# solar_collector_controller_V2.net
KiCad netlist of a schematic drawn in EAGLE
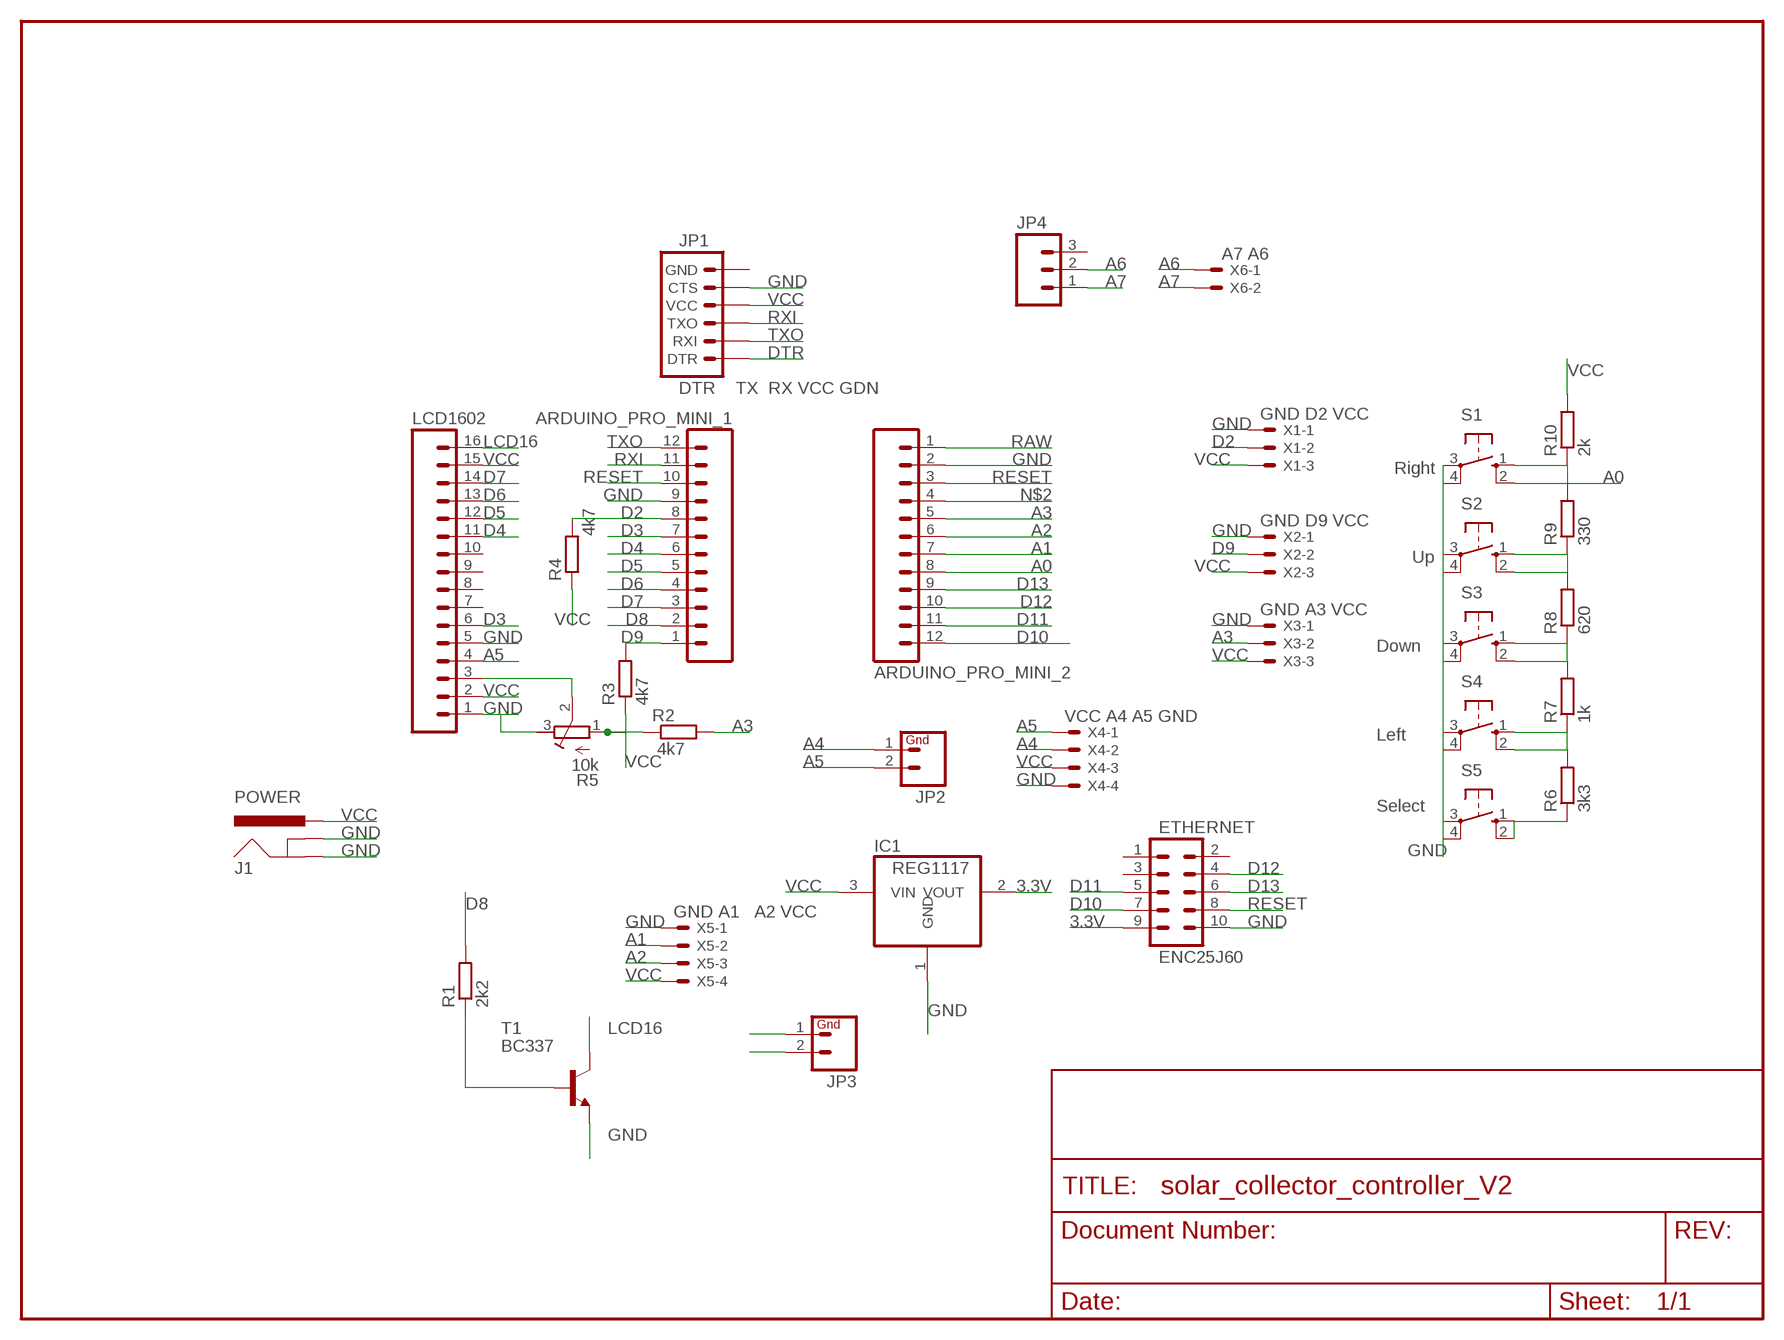
[diagram p0: schematic, sheet 1]

(export (version "E")
  (design (tool "Eeschema 10.0.6"))
  (components
    (comp (ref "ARDUINO_PRO_MINI_1")
      (value "M12PTH")
      (footprint "eagle-import:1X12")
      (libsource (lib "eagle-import") (part "M12PTH"))
    )
    (comp (ref "ARDUINO_PRO_MINI_2")
      (value "M12PTH")
      (footprint "eagle-import:1X12")
      (libsource (lib "eagle-import") (part "M12PTH"))
    )
    (comp (ref "ETHERNET")
      (value "ENC25J60")
      (footprint "eagle-import:AVR_ICSP")
      (libsource (lib "eagle-import") (part "M05X2PTH"))
    )
    (comp (ref "IC1")
      (value "REG1117")
      (footprint "eagle-import:SOT223")
      (libsource (lib "eagle-import") (part "REG1117"))
    )
    (comp (ref "J1")
      (value "POWER")
      (footprint "eagle-import:POWER_JACK_PTH_LOCK")
      (libsource (lib "eagle-import") (part "POWER_JACKPTH_LOCK"))
    )
    (comp (ref "JP1")
      (value "DTR TX RX VCC GDN")
      (footprint "eagle-import:1X06")
      (libsource (lib "eagle-import") (part "ARDUINO_SERIAL_PROGRAMPTH"))
    )
    (comp (ref "JP2")
      (value "M02PTH")
      (footprint "eagle-import:1X02")
      (libsource (lib "eagle-import") (part "M02PTH"))
    )
    (comp (ref "JP3")
      (value "M02PTH")
      (footprint "eagle-import:1X02")
      (libsource (lib "eagle-import") (part "M02PTH"))
    )
    (comp (ref "JP4")
      (value "M03PTH")
      (footprint "eagle-import:1X03")
      (libsource (lib "eagle-import") (part "M03PTH"))
    )
    (comp (ref "LCD1602")
      (value "HEADER-16P-2.54")
      (footprint "eagle-import:16P-2.54")
      (libsource (lib "eagle-import") (part "HEADER-16P-2.54"))
    )
    (comp (ref "R1")
      (value "2k2")
      (footprint "eagle-import:0207_10")
      (libsource (lib "eagle-import") (part "R-EU_0207/10"))
    )
    (comp (ref "R2")
      (value "4k7")
      (footprint "eagle-import:0207_10")
      (libsource (lib "eagle-import") (part "R-EU_0207/10"))
    )
    (comp (ref "R3")
      (value "4k7")
      (footprint "eagle-import:0207_10")
      (libsource (lib "eagle-import") (part "R-EU_0207/10"))
    )
    (comp (ref "R4")
      (value "4k7")
      (footprint "eagle-import:0207_10")
      (libsource (lib "eagle-import") (part "R-EU_0207/10"))
    )
    (comp (ref "R5")
      (value "10k")
      (footprint "eagle-import:RTRIM64W")
      (libsource (lib "eagle-import") (part "R-TRIMM64W"))
    )
    (comp (ref "R6")
      (value "3k3")
      (footprint "eagle-import:0207_10")
      (libsource (lib "eagle-import") (part "R-EU_0207/10"))
    )
    (comp (ref "R7")
      (value "1k")
      (footprint "eagle-import:0207_10")
      (libsource (lib "eagle-import") (part "R-EU_0207/10"))
    )
    (comp (ref "R8")
      (value "620")
      (footprint "eagle-import:0207_10")
      (libsource (lib "eagle-import") (part "R-EU_0207/10"))
    )
    (comp (ref "R9")
      (value "330")
      (footprint "eagle-import:0207_10")
      (libsource (lib "eagle-import") (part "R-EU_0207/10"))
    )
    (comp (ref "R10")
      (value "2k")
      (footprint "eagle-import:0207_10")
      (libsource (lib "eagle-import") (part "R-EU_0207/10"))
    )
    (comp (ref "S1")
      (value "Right")
      (footprint "eagle-import:B3F-10XX")
      (fields (field (name "MPN") "B3F-1000"))
      (libsource (lib "eagle-import") (part "10-XX"))
    )
    (comp (ref "S2")
      (value "Up")
      (footprint "eagle-import:B3F-10XX")
      (fields (field (name "MPN") "B3F-1000"))
      (libsource (lib "eagle-import") (part "10-XX"))
    )
    (comp (ref "S3")
      (value "Down")
      (footprint "eagle-import:B3F-10XX")
      (fields (field (name "MPN") "B3F-1000"))
      (libsource (lib "eagle-import") (part "10-XX"))
    )
    (comp (ref "S4")
      (value "Left")
      (footprint "eagle-import:B3F-10XX")
      (fields (field (name "MPN") "B3F-1000"))
      (libsource (lib "eagle-import") (part "10-XX"))
    )
    (comp (ref "S5")
      (value "Select")
      (footprint "eagle-import:B3F-10XX")
      (fields (field (name "MPN") "B3F-1000"))
      (libsource (lib "eagle-import") (part "10-XX"))
    )
    (comp (ref "T1")
      (value "BC337")
      (footprint "eagle-import:TO92")
      (libsource (lib "eagle-import") (part "BC337"))
    )
    (comp (ref "X1")
      (value "GND D2 VCC")
      (footprint "eagle-import:22-23-2031")
      (fields (field (name "MF") "MOLEX") (field (name "MPN") "22-23-2031"))
      (libsource (lib "eagle-import") (part "22-23-2031"))
    )
    (comp (ref "X2")
      (value "GND D9 VCC")
      (footprint "eagle-import:22-23-2031")
      (fields (field (name "MF") "MOLEX") (field (name "MPN") "22-23-2031"))
      (libsource (lib "eagle-import") (part "22-23-2031"))
    )
    (comp (ref "X3")
      (value "GND A3 VCC")
      (footprint "eagle-import:22-23-2031")
      (fields (field (name "MF") "MOLEX") (field (name "MPN") "22-23-2031"))
      (libsource (lib "eagle-import") (part "22-23-2031"))
    )
    (comp (ref "X4")
      (value "VCC A4 A5 GND")
      (footprint "eagle-import:22-23-2041")
      (fields (field (name "MF") "MOLEX") (field (name "MPN") "22-23-2041"))
      (libsource (lib "eagle-import") (part "22-23-2041"))
    )
    (comp (ref "X5")
      (value "GND A1 A2 VCC")
      (footprint "eagle-import:22-23-2041")
      (fields (field (name "MF") "MOLEX") (field (name "MPN") "22-23-2041"))
      (libsource (lib "eagle-import") (part "22-23-2041"))
    )
    (comp (ref "X6")
      (value "A7 A6")
      (footprint "eagle-import:22-23-2021")
      (fields (field (name "MF") "MOLEX") (field (name "MPN") "22-23-2021"))
      (libsource (lib "eagle-import") (part "22-23-2021"))
    )
  )
  (nets
    (net (code "1") (name "/3.3V") (class "Default")
      (node (ref "ETHERNET") (pin "9") (pinfunction "9_9") (pintype "passive"))
      (node (ref "IC1") (pin "2") (pinfunction "VOUT_2") (pintype "output"))
      (node (ref "JP3") (pin "1") (pinfunction "1_1") (pintype "passive"))
    )
    (net (code "2") (name "/A0") (class "Default")
      (node (ref "ARDUINO_PRO_MINI_2") (pin "8") (pinfunction "8_8") (pintype "passive"))
      (node (ref "R10") (pin "1") (pinfunction "1_1") (pintype "passive"))
      (node (ref "R9") (pin "2") (pinfunction "2_2") (pintype "passive"))
      (node (ref "S1") (pin "1") (pinfunction "S_1") (pintype "passive"))
      (node (ref "S1") (pin "2") (pinfunction "S1_2") (pintype "passive"))
    )
    (net (code "3") (name "/A1") (class "Default")
      (node (ref "ARDUINO_PRO_MINI_2") (pin "7") (pinfunction "7_7") (pintype "passive"))
      (node (ref "X5") (pin "2") (pinfunction "S_2") (pintype "passive"))
    )
    (net (code "4") (name "/A2") (class "Default")
      (node (ref "ARDUINO_PRO_MINI_2") (pin "6") (pinfunction "6_6") (pintype "passive"))
      (node (ref "X5") (pin "3") (pinfunction "S_3") (pintype "passive"))
    )
    (net (code "5") (name "/A3") (class "Default")
      (node (ref "ARDUINO_PRO_MINI_2") (pin "5") (pinfunction "5_5") (pintype "passive"))
      (node (ref "R2") (pin "2") (pinfunction "2_2") (pintype "passive"))
      (node (ref "X3") (pin "2") (pinfunction "S_2") (pintype "passive"))
    )
    (net (code "6") (name "/A4") (class "Default")
      (node (ref "JP2") (pin "1") (pinfunction "1_1") (pintype "passive"))
      (node (ref "X4") (pin "2") (pinfunction "S_2") (pintype "passive"))
    )
    (net (code "7") (name "/A5") (class "Default")
      (node (ref "JP2") (pin "2") (pinfunction "2_2") (pintype "passive"))
      (node (ref "LCD1602") (pin "4") (pinfunction "4_4") (pintype "passive"))
      (node (ref "X4") (pin "1") (pinfunction "S_1") (pintype "passive"))
    )
    (net (code "8") (name "/A6") (class "Default")
      (node (ref "JP4") (pin "2") (pinfunction "2_2") (pintype "passive"))
      (node (ref "X6") (pin "1") (pinfunction "S_1") (pintype "passive"))
    )
    (net (code "9") (name "/A7") (class "Default")
      (node (ref "JP4") (pin "1") (pinfunction "1_1") (pintype "passive"))
      (node (ref "X6") (pin "2") (pinfunction "S_2") (pintype "passive"))
    )
    (net (code "10") (name "/D2") (class "Default")
      (node (ref "ARDUINO_PRO_MINI_1") (pin "8") (pinfunction "8_8") (pintype "passive"))
      (node (ref "R4") (pin "2") (pinfunction "2_2") (pintype "passive"))
      (node (ref "X1") (pin "2") (pinfunction "S_2") (pintype "passive"))
    )
    (net (code "11") (name "/D3") (class "Default")
      (node (ref "ARDUINO_PRO_MINI_1") (pin "7") (pinfunction "7_7") (pintype "passive"))
      (node (ref "LCD1602") (pin "6") (pinfunction "6_6") (pintype "passive"))
    )
    (net (code "12") (name "/D4") (class "Default")
      (node (ref "ARDUINO_PRO_MINI_1") (pin "6") (pinfunction "6_6") (pintype "passive"))
      (node (ref "LCD1602") (pin "11") (pinfunction "11_11") (pintype "passive"))
    )
    (net (code "13") (name "/D5") (class "Default")
      (node (ref "ARDUINO_PRO_MINI_1") (pin "5") (pinfunction "5_5") (pintype "passive"))
      (node (ref "LCD1602") (pin "12") (pinfunction "12_12") (pintype "passive"))
    )
    (net (code "14") (name "/D6") (class "Default")
      (node (ref "ARDUINO_PRO_MINI_1") (pin "4") (pinfunction "4_4") (pintype "passive"))
      (node (ref "LCD1602") (pin "13") (pinfunction "13_13") (pintype "passive"))
    )
    (net (code "15") (name "/D7") (class "Default")
      (node (ref "ARDUINO_PRO_MINI_1") (pin "3") (pinfunction "3_3") (pintype "passive"))
      (node (ref "LCD1602") (pin "14") (pinfunction "14_14") (pintype "passive"))
    )
    (net (code "16") (name "/D8") (class "Default")
      (node (ref "ARDUINO_PRO_MINI_1") (pin "2") (pinfunction "2_2") (pintype "passive"))
      (node (ref "R1") (pin "2") (pinfunction "2_2") (pintype "passive"))
    )
    (net (code "17") (name "/D9") (class "Default")
      (node (ref "ARDUINO_PRO_MINI_1") (pin "1") (pinfunction "1_1") (pintype "passive"))
      (node (ref "R3") (pin "2") (pinfunction "2_2") (pintype "passive"))
      (node (ref "X2") (pin "2") (pinfunction "S_2") (pintype "passive"))
    )
    (net (code "18") (name "/D10") (class "Default")
      (node (ref "ARDUINO_PRO_MINI_2") (pin "12") (pinfunction "12_12") (pintype "passive"))
      (node (ref "ETHERNET") (pin "7") (pinfunction "7_7") (pintype "passive"))
    )
    (net (code "19") (name "/D11") (class "Default")
      (node (ref "ARDUINO_PRO_MINI_2") (pin "11") (pinfunction "11_11") (pintype "passive"))
      (node (ref "ETHERNET") (pin "5") (pinfunction "5_5") (pintype "passive"))
    )
    (net (code "20") (name "/D12") (class "Default")
      (node (ref "ARDUINO_PRO_MINI_2") (pin "10") (pinfunction "10_10") (pintype "passive"))
      (node (ref "ETHERNET") (pin "4") (pinfunction "4_4") (pintype "passive"))
    )
    (net (code "21") (name "/D13") (class "Default")
      (node (ref "ARDUINO_PRO_MINI_2") (pin "9") (pinfunction "9_9") (pintype "passive"))
      (node (ref "ETHERNET") (pin "6") (pinfunction "6_6") (pintype "passive"))
    )
    (net (code "22") (name "/DTR") (class "Default")
      (node (ref "JP1") (pin "1") (pinfunction "DTR_1") (pintype "passive"))
    )
    (net (code "23") (name "/GND") (class "Default")
      (node (ref "ARDUINO_PRO_MINI_1") (pin "9") (pinfunction "9_9") (pintype "passive"))
      (node (ref "ARDUINO_PRO_MINI_2") (pin "2") (pinfunction "2_2") (pintype "passive"))
      (node (ref "ETHERNET") (pin "10") (pinfunction "10_10") (pintype "passive"))
      (node (ref "IC1") (pin "1") (pinfunction "GND_1") (pintype "power_in"))
      (node (ref "J1") (pin "GND") (pinfunction "GND_GND") (pintype "bidirectional"))
      (node (ref "J1") (pin "GNDBREAK") (pinfunction "GNDBREAK_GNDBREAK") (pintype "bidirectional"))
      (node (ref "JP1") (pin "5") (pinfunction "CTS_5") (pintype "passive"))
      (node (ref "JP3") (pin "2") (pinfunction "2_2") (pintype "passive"))
      (node (ref "LCD1602") (pin "1") (pinfunction "1_1") (pintype "passive"))
      (node (ref "LCD1602") (pin "5") (pinfunction "5_5") (pintype "passive"))
      (node (ref "R5") (pin "3") (pinfunction "A_3") (pintype "passive"))
      (node (ref "S1") (pin "3") (pinfunction "P_3") (pintype "passive"))
      (node (ref "S1") (pin "4") (pinfunction "P1_4") (pintype "passive"))
      (node (ref "S2") (pin "3") (pinfunction "P_3") (pintype "passive"))
      (node (ref "S2") (pin "4") (pinfunction "P1_4") (pintype "passive"))
      (node (ref "S3") (pin "3") (pinfunction "P_3") (pintype "passive"))
      (node (ref "S3") (pin "4") (pinfunction "P1_4") (pintype "passive"))
      (node (ref "S4") (pin "3") (pinfunction "P_3") (pintype "passive"))
      (node (ref "S4") (pin "4") (pinfunction "P1_4") (pintype "passive"))
      (node (ref "S5") (pin "3") (pinfunction "P_3") (pintype "passive"))
      (node (ref "S5") (pin "4") (pinfunction "P1_4") (pintype "passive"))
      (node (ref "T1") (pin "1") (pinfunction "E_1") (pintype "passive"))
      (node (ref "X1") (pin "1") (pinfunction "S_1") (pintype "passive"))
      (node (ref "X2") (pin "1") (pinfunction "S_1") (pintype "passive"))
      (node (ref "X3") (pin "1") (pinfunction "S_1") (pintype "passive"))
      (node (ref "X4") (pin "4") (pinfunction "S_4") (pintype "passive"))
      (node (ref "X5") (pin "1") (pinfunction "S_1") (pintype "passive"))
    )
    (net (code "24") (name "/LCD16") (class "Default")
      (node (ref "LCD1602") (pin "16") (pinfunction "16_16") (pintype "passive"))
      (node (ref "T1") (pin "3") (pinfunction "C_3") (pintype "passive"))
    )
    (net (code "25") (name "/N$2") (class "Default")
      (node (ref "ARDUINO_PRO_MINI_2") (pin "4") (pinfunction "4_4") (pintype "passive"))
    )
    (net (code "26") (name "/RAW") (class "Default")
      (node (ref "ARDUINO_PRO_MINI_2") (pin "1") (pinfunction "1_1") (pintype "passive"))
    )
    (net (code "27") (name "/RESET") (class "Default")
      (node (ref "ARDUINO_PRO_MINI_1") (pin "10") (pinfunction "10_10") (pintype "passive"))
      (node (ref "ARDUINO_PRO_MINI_2") (pin "3") (pinfunction "3_3") (pintype "passive"))
      (node (ref "ETHERNET") (pin "8") (pinfunction "8_8") (pintype "passive"))
    )
    (net (code "28") (name "/RXI") (class "Default")
      (node (ref "ARDUINO_PRO_MINI_1") (pin "11") (pinfunction "11_11") (pintype "passive"))
      (node (ref "JP1") (pin "3") (pinfunction "TXO_3") (pintype "passive"))
    )
    (net (code "29") (name "/TXO") (class "Default")
      (node (ref "ARDUINO_PRO_MINI_1") (pin "12") (pinfunction "12_12") (pintype "passive"))
      (node (ref "JP1") (pin "2") (pinfunction "RXI_2") (pintype "passive"))
    )
    (net (code "30") (name "/VCC") (class "Default")
      (node (ref "IC1") (pin "3") (pinfunction "VIN_3") (pintype "input"))
      (node (ref "J1") (pin "PWR") (pinfunction "PWR_PWR") (pintype "bidirectional"))
      (node (ref "JP1") (pin "4") (pinfunction "VCC_4") (pintype "passive"))
      (node (ref "LCD1602") (pin "15") (pinfunction "15_15") (pintype "passive"))
      (node (ref "LCD1602") (pin "2") (pinfunction "2_2") (pintype "passive"))
      (node (ref "R10") (pin "2") (pinfunction "2_2") (pintype "passive"))
      (node (ref "R2") (pin "1") (pinfunction "1_1") (pintype "passive"))
      (node (ref "R3") (pin "1") (pinfunction "1_1") (pintype "passive"))
      (node (ref "R4") (pin "1") (pinfunction "1_1") (pintype "passive"))
      (node (ref "R5") (pin "1") (pinfunction "E_1") (pintype "passive"))
      (node (ref "X1") (pin "3") (pinfunction "S_3") (pintype "passive"))
      (node (ref "X2") (pin "3") (pinfunction "S_3") (pintype "passive"))
      (node (ref "X3") (pin "3") (pinfunction "S_3") (pintype "passive"))
      (node (ref "X4") (pin "3") (pinfunction "S_3") (pintype "passive"))
      (node (ref "X5") (pin "4") (pinfunction "S_4") (pintype "passive"))
    )
    (net (code "31") (name "Net-(R5-S)") (class "Default")
      (node (ref "LCD1602") (pin "3") (pinfunction "3_3") (pintype "passive"))
      (node (ref "R5") (pin "2") (pinfunction "S_2") (pintype "passive"))
    )
    (net (code "32") (name "Net-(S2-S)") (class "Default")
      (node (ref "R8") (pin "2") (pinfunction "2_2") (pintype "passive"))
      (node (ref "R9") (pin "1") (pinfunction "1_1") (pintype "passive"))
      (node (ref "S2") (pin "1") (pinfunction "S_1") (pintype "passive"))
      (node (ref "S2") (pin "2") (pinfunction "S1_2") (pintype "passive"))
    )
    (net (code "33") (name "Net-(S3-S)") (class "Default")
      (node (ref "R7") (pin "2") (pinfunction "2_2") (pintype "passive"))
      (node (ref "R8") (pin "1") (pinfunction "1_1") (pintype "passive"))
      (node (ref "S3") (pin "1") (pinfunction "S_1") (pintype "passive"))
      (node (ref "S3") (pin "2") (pinfunction "S1_2") (pintype "passive"))
    )
    (net (code "34") (name "Net-(S4-S)") (class "Default")
      (node (ref "R6") (pin "2") (pinfunction "2_2") (pintype "passive"))
      (node (ref "R7") (pin "1") (pinfunction "1_1") (pintype "passive"))
      (node (ref "S4") (pin "1") (pinfunction "S_1") (pintype "passive"))
      (node (ref "S4") (pin "2") (pinfunction "S1_2") (pintype "passive"))
    )
    (net (code "35") (name "Net-(S5-S)") (class "Default")
      (node (ref "R6") (pin "1") (pinfunction "1_1") (pintype "passive"))
      (node (ref "S5") (pin "1") (pinfunction "S_1") (pintype "passive"))
      (node (ref "S5") (pin "2") (pinfunction "S1_2") (pintype "passive"))
    )
    (net (code "36") (name "Net-(T1-B)") (class "Default")
      (node (ref "R1") (pin "1") (pinfunction "1_1") (pintype "passive"))
      (node (ref "T1") (pin "2") (pinfunction "B_2") (pintype "passive"))
    )
    (net (code "37") (name "unconnected-(ETHERNET-Pad1)") (class "Default")
      (node (ref "ETHERNET") (pin "1") (pinfunction "1_1") (pintype "passive"))
    )
    (net (code "38") (name "unconnected-(ETHERNET-Pad2)") (class "Default")
      (node (ref "ETHERNET") (pin "2") (pinfunction "2_2") (pintype "passive"))
    )
    (net (code "39") (name "unconnected-(ETHERNET-Pad3)") (class "Default")
      (node (ref "ETHERNET") (pin "3") (pinfunction "3_3") (pintype "passive"))
    )
    (net (code "40") (name "unconnected-(JP1-GND-Pad6)") (class "Default")
      (node (ref "JP1") (pin "6") (pinfunction "GND_6") (pintype "passive"))
    )
    (net (code "41") (name "unconnected-(JP4-Pad3)") (class "Default")
      (node (ref "JP4") (pin "3") (pinfunction "3_3") (pintype "passive"))
    )
    (net (code "42") (name "unconnected-(LCD1602-Pad7)") (class "Default")
      (node (ref "LCD1602") (pin "7") (pinfunction "7_7") (pintype "passive"))
    )
    (net (code "43") (name "unconnected-(LCD1602-Pad8)") (class "Default")
      (node (ref "LCD1602") (pin "8") (pinfunction "8_8") (pintype "passive"))
    )
    (net (code "44") (name "unconnected-(LCD1602-Pad9)") (class "Default")
      (node (ref "LCD1602") (pin "9") (pinfunction "9_9") (pintype "passive"))
    )
    (net (code "45") (name "unconnected-(LCD1602-Pad10)") (class "Default")
      (node (ref "LCD1602") (pin "10") (pinfunction "10_10") (pintype "passive"))
    )
  )
)
